# night-activated-switch.net
KiCad netlist of a schematic drawn in EAGLE
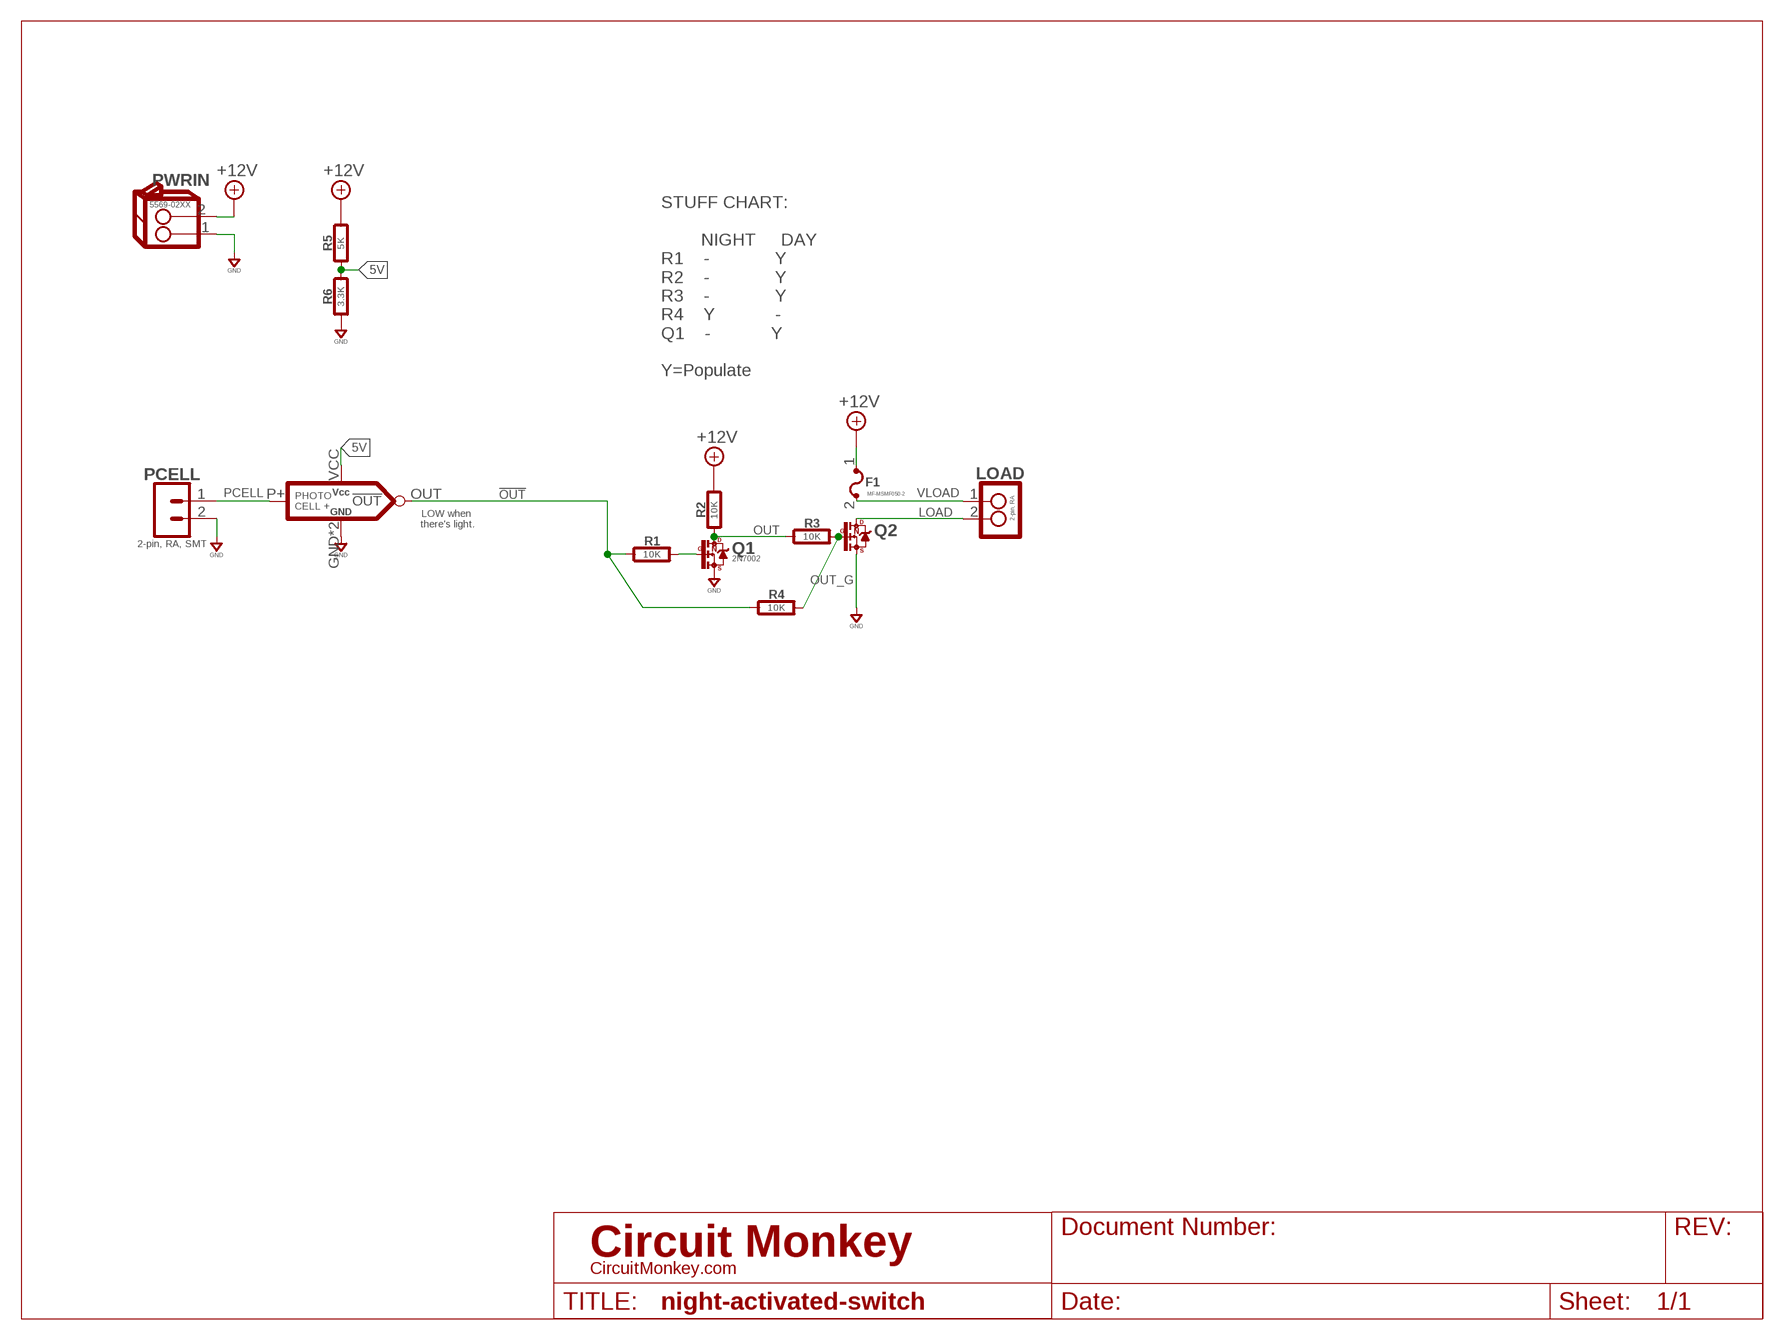
[diagram p0: schematic, sheet 1]

(export (version "E")
  (design (tool "Eeschema 10.0.6"))
  (components
    (comp (ref "F1")
      (value "MF-MSMF050-2")
      (footprint "eagle-import:BOURNS-MF-MSMF")
      (libsource (lib "eagle-import") (part "FUSEBOURNS-MF-MSMF"))
    )
    (comp (ref "LOAD")
      (value "2-pin, RA")
      (footprint "eagle-import:MOLEX-105313-XX02")
      (fields (field (name "MFR") "Molex") (field (name "MPN") "105313-xx02"))
      (libsource (lib "eagle-import") (part "NANOFIT-02P-SR"))
    )
    (comp (ref "LS1")
      (value "Light Sensor")
      (footprint "eagle-import:LIGHT-SENSOR-MODULE-B07QKJPWCG")
      (fields (field (name "MFR") "Amazon") (field (name "MPN") "B07QKJPWCG"))
      (libsource (lib "eagle-import") (part "LIGHT-SENSORB07QKJPWCG"))
    )
    (comp (ref "PCELL")
      (value "2-pin, RA, SMT")
      (footprint "eagle-import:S2B-PH-SM4-")
      (fields (field (name "MFR") "JST") (field (name "MPN") "S2B-PH-SM4"))
      (libsource (lib "eagle-import") (part "02PRA-SMT"))
    )
    (comp (ref "PWRIN")
      (value "5569-02XX")
      (footprint "eagle-import:MOLEX-5569-02XX")
      (libsource (lib "eagle-import") (part "MINIFIT-JR-02P-RA"))
    )
    (comp (ref "Q1")
      (value "2N7002")
      (footprint "eagle-import:SOT-23")
      (libsource (lib "eagle-import") (part "N-FET_2N7002"))
    )
    (comp (ref "Q2")
      (value "N-FET_SI2318A")
      (footprint "eagle-import:SOT-23")
      (libsource (lib "eagle-import") (part "N-FET_SI2318A"))
    )
    (comp (ref "R1")
      (value "10K")
      (footprint "eagle-import:0603-RES")
      (libsource (lib "eagle-import") (part "RESISTOR0603"))
    )
    (comp (ref "R2")
      (value "10K")
      (footprint "eagle-import:0603-RES")
      (libsource (lib "eagle-import") (part "RESISTOR0603"))
    )
    (comp (ref "R3")
      (value "10K")
      (footprint "eagle-import:0603-RES")
      (libsource (lib "eagle-import") (part "RESISTOR0603"))
    )
    (comp (ref "R4")
      (value "10K")
      (footprint "eagle-import:0603-RES")
      (libsource (lib "eagle-import") (part "RESISTOR0603"))
    )
    (comp (ref "R5")
      (value "5K")
      (footprint "eagle-import:0603-RES")
      (libsource (lib "eagle-import") (part "RESISTOR0603"))
    )
    (comp (ref "R6")
      (value "3.3K")
      (footprint "eagle-import:0603-RES")
      (libsource (lib "eagle-import") (part "RESISTOR0603"))
    )
  )
  (nets
    (net (code "1") (name "+12V") (class "Default")
      (node (ref "F1") (pin "1") (pinfunction "1_1") (pintype "bidirectional"))
      (node (ref "PWRIN") (pin "2") (pinfunction "2_2") (pintype "bidirectional"))
      (node (ref "R2") (pin "1") (pinfunction "1_1") (pintype "passive"))
      (node (ref "R5") (pin "1") (pinfunction "1_1") (pintype "passive"))
    )
    (net (code "2") (name "/LOAD") (class "Default")
      (node (ref "LOAD") (pin "2") (pinfunction "2_2") (pintype "bidirectional"))
      (node (ref "Q2") (pin "3") (pinfunction "D_3") (pintype "bidirectional"))
    )
    (net (code "3") (name "/OUT") (class "Default")
      (node (ref "Q1") (pin "3") (pinfunction "D_3") (pintype "bidirectional"))
      (node (ref "R2") (pin "2") (pinfunction "2_2") (pintype "passive"))
      (node (ref "R3") (pin "1") (pinfunction "1_1") (pintype "passive"))
    )
    (net (code "4") (name "/OUT_G") (class "Default")
      (node (ref "Q2") (pin "1") (pinfunction "G_1") (pintype "bidirectional"))
      (node (ref "R3") (pin "2") (pinfunction "2_2") (pintype "passive"))
      (node (ref "R4") (pin "2") (pinfunction "2_2") (pintype "passive"))
    )
    (net (code "5") (name "/PCELL") (class "Default")
      (node (ref "LS1") (pin "P+") (pinfunction "CELL_P+") (pintype "input"))
      (node (ref "PCELL") (pin "1") (pinfunction "1_1") (pintype "passive"))
    )
    (net (code "6") (name "/VLOAD") (class "Default")
      (node (ref "F1") (pin "2") (pinfunction "2_2") (pintype "bidirectional"))
      (node (ref "LOAD") (pin "1") (pinfunction "1_1") (pintype "bidirectional"))
    )
    (net (code "7") (name "/~{OUT}") (class "Default")
      (node (ref "LS1") (pin "OUT") (pinfunction "OUT_OUT") (pintype "output"))
      (node (ref "R1") (pin "1") (pinfunction "1_1") (pintype "passive"))
      (node (ref "R4") (pin "1") (pinfunction "1_1") (pintype "passive"))
    )
    (net (code "8") (name "5V") (class "Default")
      (node (ref "LS1") (pin "VCC") (pinfunction "VCC_VCC") (pintype "power_in"))
      (node (ref "R5") (pin "2") (pinfunction "2_2") (pintype "passive"))
      (node (ref "R6") (pin "1") (pinfunction "1_1") (pintype "passive"))
    )
    (net (code "9") (name "GND") (class "Default")
      (node (ref "LS1") (pin "GND") (pinfunction "GND_GND") (pintype "power_in"))
      (node (ref "LS1") (pin "P-") (pinfunction "GND_P-") (pintype "power_in"))
      (node (ref "PCELL") (pin "2") (pinfunction "2_2") (pintype "passive"))
      (node (ref "PWRIN") (pin "1") (pinfunction "1_1") (pintype "bidirectional"))
      (node (ref "Q1") (pin "2") (pinfunction "S_2") (pintype "bidirectional"))
      (node (ref "Q2") (pin "2") (pinfunction "S_2") (pintype "bidirectional"))
      (node (ref "R6") (pin "2") (pinfunction "2_2") (pintype "passive"))
    )
    (net (code "10") (name "Net-(Q1-G)") (class "Default")
      (node (ref "Q1") (pin "1") (pinfunction "G_1") (pintype "bidirectional"))
      (node (ref "R1") (pin "2") (pinfunction "2_2") (pintype "passive"))
    )
  )
)
